# 16_SOLENOID_HB_1.net
KiCad netlist of a schematic drawn in Altium Designer
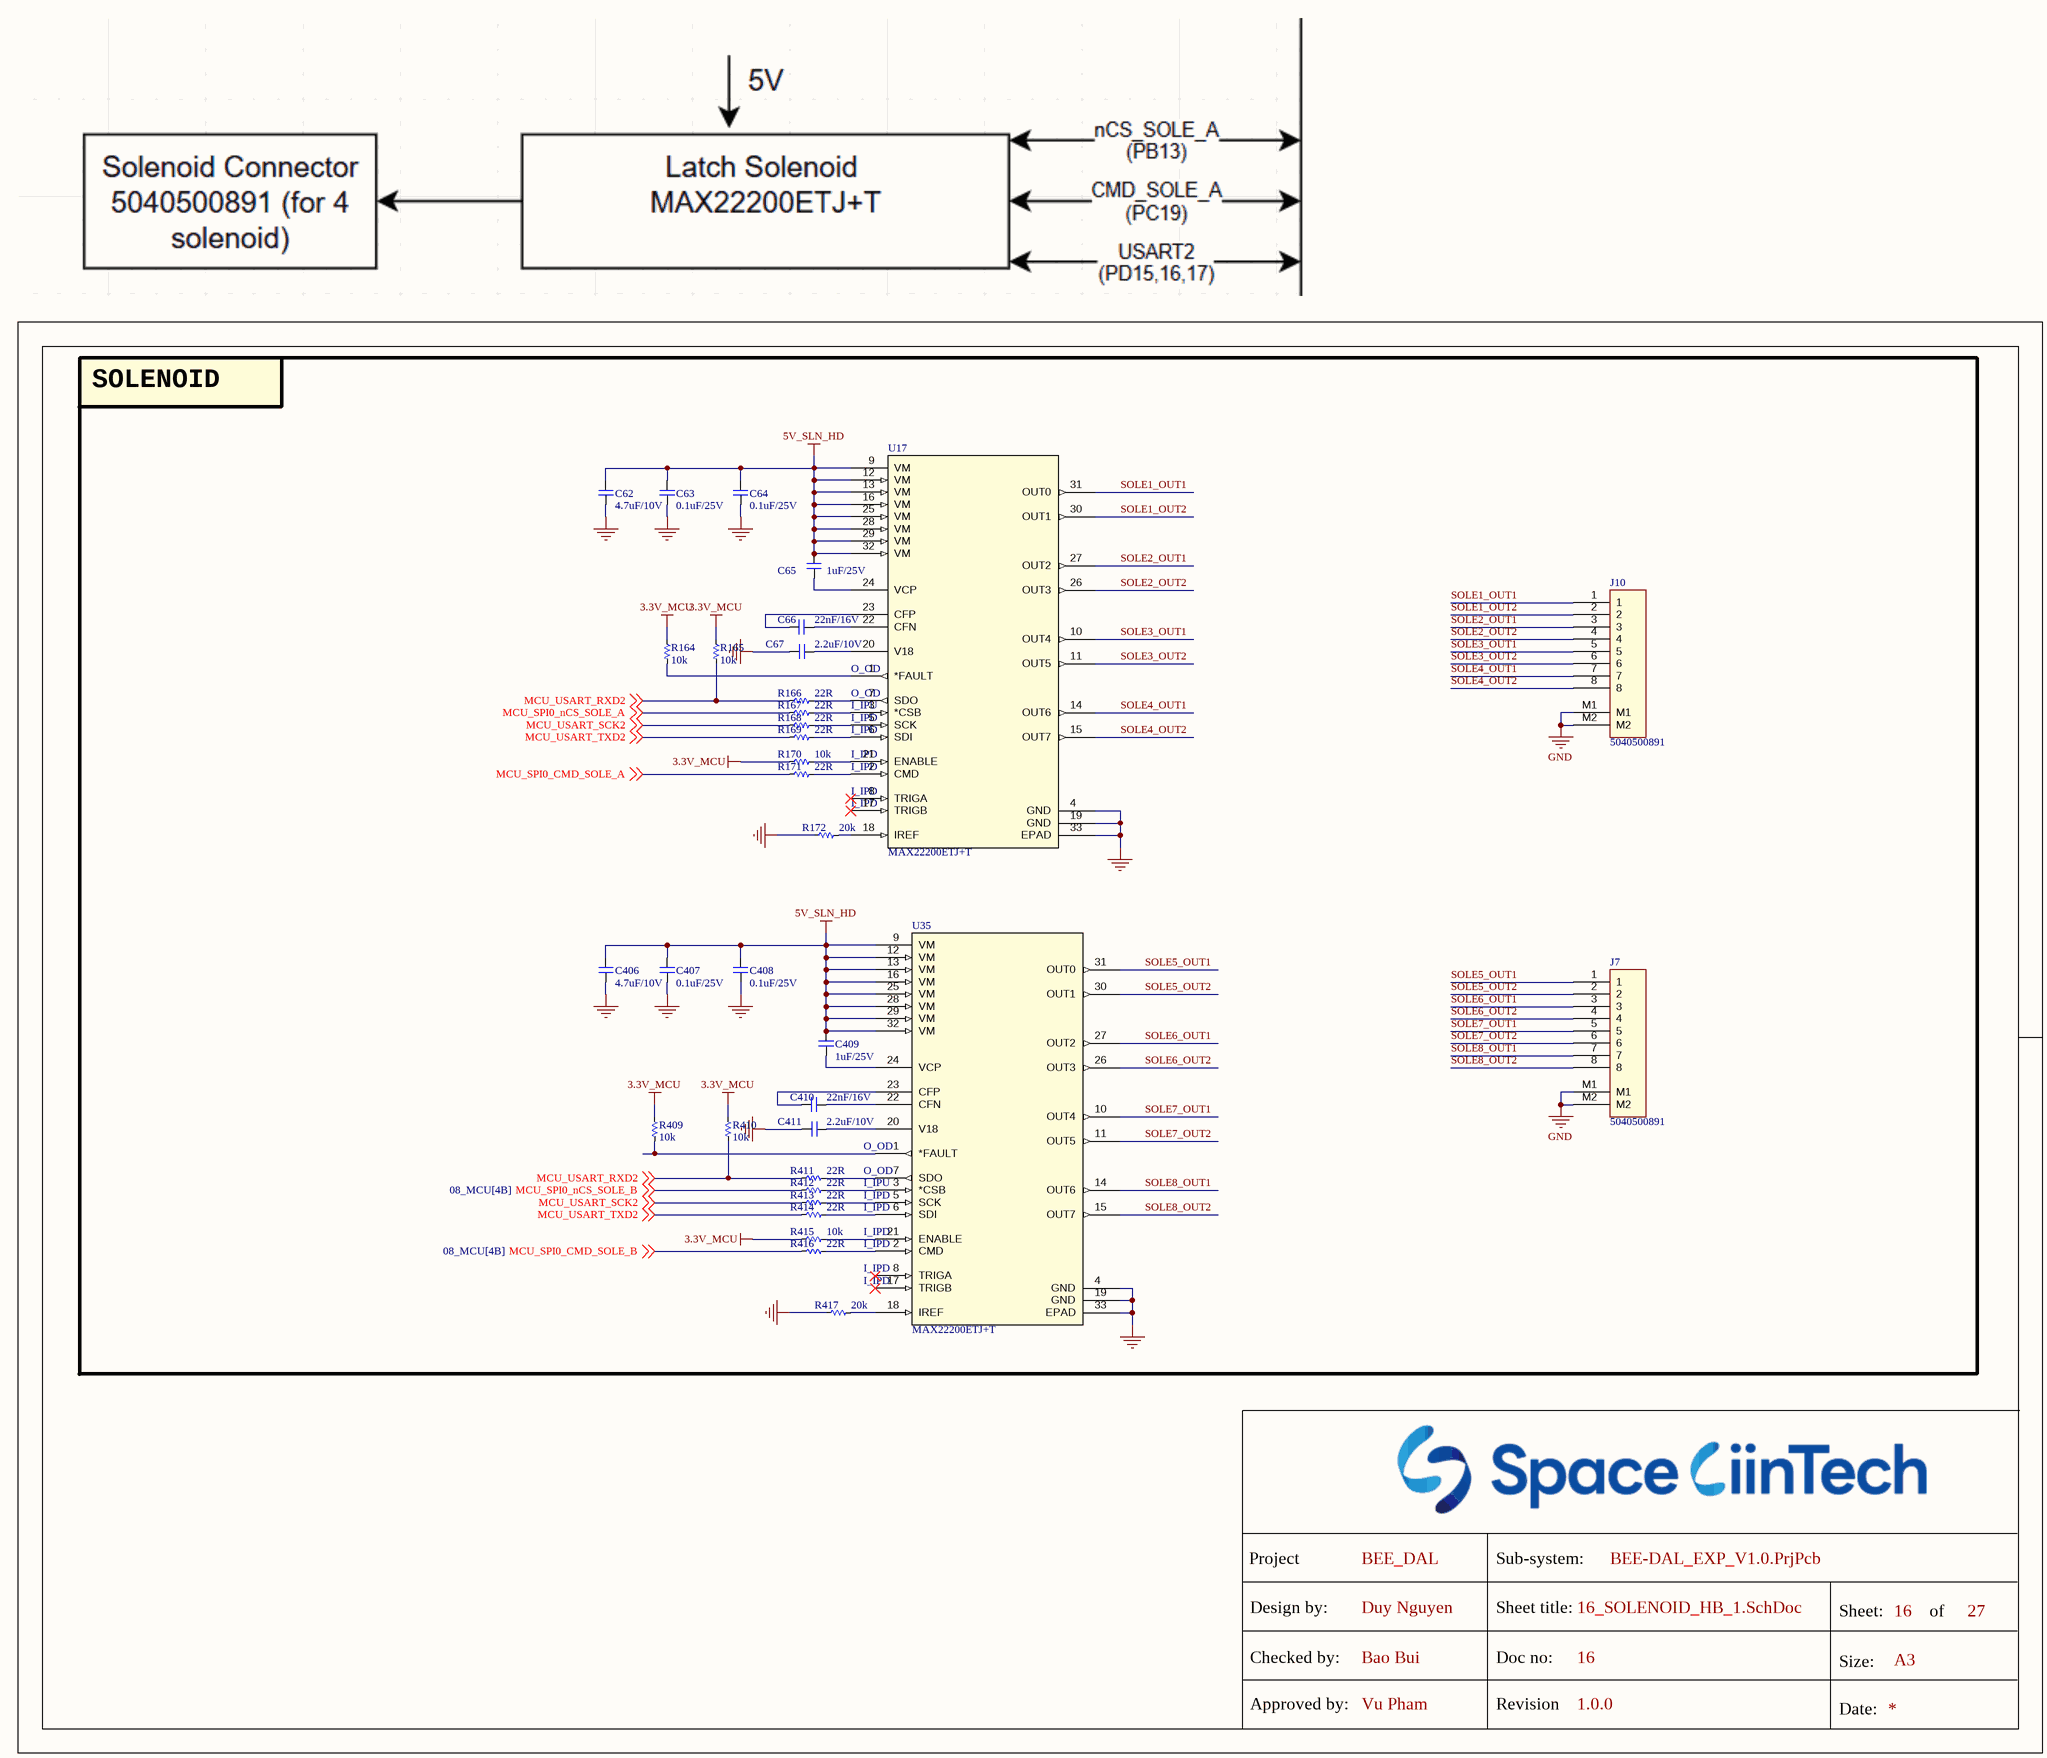
[diagram p0: 16_SOLENOID_HB_1.SchDoc]

(export (version "E")
  (design (tool "Eeschema 10.0.6"))
  (components
    (comp (ref "C62")
      (value "4.7uF/10V")
      (footprint "CAP_C_1005X60")
      (description "CAP")
      (libsource (lib "LABLIB") (part "_CAP_C_2"))
    )
    (comp (ref "C63")
      (value "0.1uF/25V")
      (footprint "CAP_C_1005X60")
      (description "CAP")
      (libsource (lib "LABLIB") (part "_CAP_C_2"))
    )
    (comp (ref "C64")
      (value "0.1uF/25V")
      (footprint "CAP_C_1005X60")
      (description "CAP")
      (libsource (lib "LABLIB") (part "_CAP_C_2"))
    )
    (comp (ref "C65")
      (value "1uF/25V")
      (footprint "CAP_C_1005X60")
      (description "CAP")
      (libsource (lib "LABLIB") (part "_CAP_C_2"))
    )
    (comp (ref "C66")
      (value "22nF/16V")
      (footprint "CAP_C_1005X60")
      (description "CAP CHIP")
      (libsource (lib "LABLIB") (part "_CAP_C_2"))
    )
    (comp (ref "C67")
      (value "2.2uF/10V")
      (footprint "CAP_C_1005X60")
      (description "CAP")
      (libsource (lib "LABLIB") (part "_CAP_C_2"))
    )
    (comp (ref "C406")
      (value "4.7uF/10V")
      (footprint "CAP_C_1005X60")
      (description "CAP")
      (libsource (lib "LABLIB") (part "_CAP_C_2"))
    )
    (comp (ref "C407")
      (value "0.1uF/25V")
      (footprint "CAP_C_1005X60")
      (description "CAP")
      (libsource (lib "LABLIB") (part "_CAP_C_2"))
    )
    (comp (ref "C408")
      (value "0.1uF/25V")
      (footprint "CAP_C_1005X60")
      (description "CAP")
      (libsource (lib "LABLIB") (part "_CAP_C_2"))
    )
    (comp (ref "C409")
      (value "1uF/25V")
      (footprint "CAP_C_1005X60")
      (description "CAP")
      (libsource (lib "LABLIB") (part "_CAP_C_2"))
    )
    (comp (ref "C410")
      (value "22nF/16V")
      (footprint "CAP_C_1005X60")
      (description "CAP CHIP")
      (libsource (lib "LABLIB") (part "_CAP_C_2"))
    )
    (comp (ref "C411")
      (value "2.2uF/10V")
      (footprint "CAP_C_1005X60")
      (description "CAP")
      (libsource (lib "LABLIB") (part "_CAP_C_2"))
    )
    (comp (ref "J7")
      (value "5040500891")
      (footprint "MOLEX_5040500891")
      (libsource (lib "LABLIB") (part "Header 8x1_2M"))
    )
    (comp (ref "J10")
      (value "5040500891")
      (footprint "MOLEX_5040500891")
      (libsource (lib "LABLIB") (part "Header 8x1_2M"))
    )
    (comp (ref "R164")
      (value "10k")
      (footprint "RES_C_1005X40")
      (description "RES")
      (libsource (lib "LABLIB") (part "_RES_B_2"))
    )
    (comp (ref "R165")
      (value "10k")
      (footprint "RES_C_1005X40")
      (description "RES")
      (libsource (lib "LABLIB") (part "_RES_B_2"))
    )
    (comp (ref "R166")
      (value "22R")
      (footprint "RES_C_1005X40")
      (description "RES")
      (libsource (lib "LABLIB") (part "_RES_B_2"))
    )
    (comp (ref "R167")
      (value "22R")
      (footprint "RES_C_1005X40")
      (description "RES")
      (libsource (lib "LABLIB") (part "_RES_B_2"))
    )
    (comp (ref "R168")
      (value "22R")
      (footprint "RES_C_1005X40")
      (description "RES")
      (libsource (lib "LABLIB") (part "_RES_B_2"))
    )
    (comp (ref "R169")
      (value "22R")
      (footprint "RES_C_1005X40")
      (description "RES")
      (libsource (lib "LABLIB") (part "_RES_B_2"))
    )
    (comp (ref "R170")
      (value "10k")
      (footprint "RES_C_1005X40")
      (description "RES")
      (libsource (lib "LABLIB") (part "_RES_B_2"))
    )
    (comp (ref "R171")
      (value "22R")
      (footprint "RES_C_1005X40")
      (description "RES")
      (libsource (lib "LABLIB") (part "_RES_B_2"))
    )
    (comp (ref "R172")
      (value "20k")
      (footprint "RES_C_1005X40")
      (description "RES")
      (libsource (lib "LABLIB") (part "_RES_B_2"))
    )
    (comp (ref "R409")
      (value "10k")
      (footprint "RES_C_1005X40")
      (description "RES")
      (libsource (lib "LABLIB") (part "_RES_B_2"))
    )
    (comp (ref "R410")
      (value "10k")
      (footprint "RES_C_1005X40")
      (description "RES")
      (libsource (lib "LABLIB") (part "_RES_B_2"))
    )
    (comp (ref "R411")
      (value "22R")
      (footprint "RES_C_1005X40")
      (description "RES")
      (libsource (lib "LABLIB") (part "_RES_B_2"))
    )
    (comp (ref "R412")
      (value "22R")
      (footprint "RES_C_1005X40")
      (description "RES")
      (libsource (lib "LABLIB") (part "_RES_B_2"))
    )
    (comp (ref "R413")
      (value "22R")
      (footprint "RES_C_1005X40")
      (description "RES")
      (libsource (lib "LABLIB") (part "_RES_B_2"))
    )
    (comp (ref "R414")
      (value "22R")
      (footprint "RES_C_1005X40")
      (description "RES")
      (libsource (lib "LABLIB") (part "_RES_B_2"))
    )
    (comp (ref "R415")
      (value "10k")
      (footprint "RES_C_1005X40")
      (description "RES")
      (libsource (lib "LABLIB") (part "_RES_B_2"))
    )
    (comp (ref "R416")
      (value "22R")
      (footprint "RES_C_1005X40")
      (description "RES")
      (libsource (lib "LABLIB") (part "_RES_B_2"))
    )
    (comp (ref "R417")
      (value "20k")
      (footprint "RES_C_1005X40")
      (description "RES")
      (libsource (lib "LABLIB") (part "_RES_B_2"))
    )
    (comp (ref "U17")
      (value "MAX22200ETJ+T")
      (footprint "21-0140AK_T3255_8C_MXM")
      (description "36V, 1A Octal Integrated Serial-Controlled Solenoid and Motor Driver")
      (fields (field (name "COPYRIGHT") "Copyright (C) 2026 Ultra Librarian. All rights reserved."))
      (libsource (lib "LABLIB") (part "MAX22200ETJ+T"))
    )
    (comp (ref "U35")
      (value "MAX22200ETJ+T")
      (footprint "21-0140AK_T3255_8C_MXM")
      (description "36V, 1A Octal Integrated Serial-Controlled Solenoid and Motor Driver")
      (fields (field (name "COPYRIGHT") "Copyright (C) 2026 Ultra Librarian. All rights reserved."))
      (libsource (lib "LABLIB") (part "MAX22200ETJ+T"))
    )
  )
  (nets
    (net (code "1") (name "/SOLE1_OUT1") (class "Default")
      (node (ref "J10") (pin "1") (pinfunction "1_1") (pintype "passive"))
      (node (ref "U17") (pin "31") (pinfunction "OUT0_31") (pintype "output"))
    )
    (net (code "2") (name "/SOLE1_OUT2") (class "Default")
      (node (ref "J10") (pin "2") (pinfunction "2_2") (pintype "passive"))
      (node (ref "U17") (pin "30") (pinfunction "OUT1_30") (pintype "output"))
    )
    (net (code "3") (name "/SOLE2_OUT1") (class "Default")
      (node (ref "J10") (pin "3") (pinfunction "3_3") (pintype "passive"))
      (node (ref "U17") (pin "27") (pinfunction "OUT2_27") (pintype "output"))
    )
    (net (code "4") (name "/SOLE2_OUT2") (class "Default")
      (node (ref "J10") (pin "4") (pinfunction "4_4") (pintype "passive"))
      (node (ref "U17") (pin "26") (pinfunction "OUT3_26") (pintype "output"))
    )
    (net (code "5") (name "/SOLE3_OUT1") (class "Default")
      (node (ref "J10") (pin "5") (pinfunction "5_5") (pintype "passive"))
      (node (ref "U17") (pin "10") (pinfunction "OUT4_10") (pintype "output"))
    )
    (net (code "6") (name "/SOLE3_OUT2") (class "Default")
      (node (ref "J10") (pin "6") (pinfunction "6_6") (pintype "passive"))
      (node (ref "U17") (pin "11") (pinfunction "OUT5_11") (pintype "output"))
    )
    (net (code "7") (name "/SOLE4_OUT1") (class "Default")
      (node (ref "J10") (pin "7") (pinfunction "7_7") (pintype "passive"))
      (node (ref "U17") (pin "14") (pinfunction "OUT6_14") (pintype "output"))
    )
    (net (code "8") (name "/SOLE4_OUT2") (class "Default")
      (node (ref "J10") (pin "8") (pinfunction "8_8") (pintype "passive"))
      (node (ref "U17") (pin "15") (pinfunction "OUT7_15") (pintype "output"))
    )
    (net (code "9") (name "/SOLE5_OUT1") (class "Default")
      (node (ref "J7") (pin "1") (pinfunction "1_1") (pintype "passive"))
      (node (ref "U35") (pin "31") (pinfunction "OUT0_31") (pintype "output"))
    )
    (net (code "10") (name "/SOLE5_OUT2") (class "Default")
      (node (ref "J7") (pin "2") (pinfunction "2_2") (pintype "passive"))
      (node (ref "U35") (pin "30") (pinfunction "OUT1_30") (pintype "output"))
    )
    (net (code "11") (name "/SOLE6_OUT1") (class "Default")
      (node (ref "J7") (pin "3") (pinfunction "3_3") (pintype "passive"))
      (node (ref "U35") (pin "27") (pinfunction "OUT2_27") (pintype "output"))
    )
    (net (code "12") (name "/SOLE6_OUT2") (class "Default")
      (node (ref "J7") (pin "4") (pinfunction "4_4") (pintype "passive"))
      (node (ref "U35") (pin "26") (pinfunction "OUT3_26") (pintype "output"))
    )
    (net (code "13") (name "/SOLE7_OUT1") (class "Default")
      (node (ref "J7") (pin "5") (pinfunction "5_5") (pintype "passive"))
      (node (ref "U35") (pin "10") (pinfunction "OUT4_10") (pintype "output"))
    )
    (net (code "14") (name "/SOLE7_OUT2") (class "Default")
      (node (ref "J7") (pin "6") (pinfunction "6_6") (pintype "passive"))
      (node (ref "U35") (pin "11") (pinfunction "OUT5_11") (pintype "output"))
    )
    (net (code "15") (name "/SOLE8_OUT1") (class "Default")
      (node (ref "J7") (pin "7") (pinfunction "7_7") (pintype "passive"))
      (node (ref "U35") (pin "14") (pinfunction "OUT6_14") (pintype "output"))
    )
    (net (code "16") (name "/SOLE8_OUT2") (class "Default")
      (node (ref "J7") (pin "8") (pinfunction "8_8") (pintype "passive"))
      (node (ref "U35") (pin "15") (pinfunction "OUT7_15") (pintype "output"))
    )
    (net (code "17") (name "3.3V_MCU") (class "Default")
      (node (ref "R164") (pin "1") (pinfunction "1_1") (pintype "passive"))
      (node (ref "R165") (pin "1") (pinfunction "1_1") (pintype "passive"))
      (node (ref "R170") (pin "1") (pinfunction "1_1") (pintype "passive"))
      (node (ref "R409") (pin "1") (pinfunction "1_1") (pintype "passive"))
      (node (ref "R410") (pin "1") (pinfunction "1_1") (pintype "passive"))
      (node (ref "R415") (pin "1") (pinfunction "1_1") (pintype "passive"))
    )
    (net (code "18") (name "5V_SLN_HD") (class "Default")
      (node (ref "C406") (pin "2") (pinfunction "2_2") (pintype "passive"))
      (node (ref "C407") (pin "2") (pinfunction "2_2") (pintype "passive"))
      (node (ref "C408") (pin "2") (pinfunction "2_2") (pintype "passive"))
      (node (ref "C409") (pin "2") (pinfunction "2_2") (pintype "passive"))
      (node (ref "C62") (pin "2") (pinfunction "2_2") (pintype "passive"))
      (node (ref "C63") (pin "2") (pinfunction "2_2") (pintype "passive"))
      (node (ref "C64") (pin "2") (pinfunction "2_2") (pintype "passive"))
      (node (ref "C65") (pin "2") (pinfunction "2_2") (pintype "passive"))
      (node (ref "U17") (pin "12") (pinfunction "VM_12") (pintype "input"))
      (node (ref "U17") (pin "13") (pinfunction "VM_13") (pintype "input"))
      (node (ref "U17") (pin "16") (pinfunction "VM_16") (pintype "input"))
      (node (ref "U17") (pin "25") (pinfunction "VM_25") (pintype "input"))
      (node (ref "U17") (pin "28") (pinfunction "VM_28") (pintype "input"))
      (node (ref "U17") (pin "29") (pinfunction "VM_29") (pintype "input"))
      (node (ref "U17") (pin "32") (pinfunction "VM_32") (pintype "input"))
      (node (ref "U17") (pin "9") (pinfunction "VM_9") (pintype "power_in"))
      (node (ref "U35") (pin "12") (pinfunction "VM_12") (pintype "input"))
      (node (ref "U35") (pin "13") (pinfunction "VM_13") (pintype "input"))
      (node (ref "U35") (pin "16") (pinfunction "VM_16") (pintype "input"))
      (node (ref "U35") (pin "25") (pinfunction "VM_25") (pintype "input"))
      (node (ref "U35") (pin "28") (pinfunction "VM_28") (pintype "input"))
      (node (ref "U35") (pin "29") (pinfunction "VM_29") (pintype "input"))
      (node (ref "U35") (pin "32") (pinfunction "VM_32") (pintype "input"))
      (node (ref "U35") (pin "9") (pinfunction "VM_9") (pintype "power_in"))
    )
    (net (code "19") (name "GND") (class "Default")
      (node (ref "C406") (pin "1") (pinfunction "1_1") (pintype "passive"))
      (node (ref "C407") (pin "1") (pinfunction "1_1") (pintype "passive"))
      (node (ref "C408") (pin "1") (pinfunction "1_1") (pintype "passive"))
      (node (ref "C411") (pin "1") (pinfunction "1_1") (pintype "passive"))
      (node (ref "C62") (pin "1") (pinfunction "1_1") (pintype "passive"))
      (node (ref "C63") (pin "1") (pinfunction "1_1") (pintype "passive"))
      (node (ref "C64") (pin "1") (pinfunction "1_1") (pintype "passive"))
      (node (ref "C67") (pin "1") (pinfunction "1_1") (pintype "passive"))
      (node (ref "J10") (pin "M1") (pinfunction "M1_M1") (pintype "passive"))
      (node (ref "J10") (pin "M2") (pinfunction "M2_M2") (pintype "passive"))
      (node (ref "J7") (pin "M1") (pinfunction "M1_M1") (pintype "passive"))
      (node (ref "J7") (pin "M2") (pinfunction "M2_M2") (pintype "passive"))
      (node (ref "R172") (pin "1") (pinfunction "1_1") (pintype "passive"))
      (node (ref "R417") (pin "1") (pinfunction "1_1") (pintype "passive"))
      (node (ref "U17") (pin "19") (pinfunction "GND_19") (pintype "power_in"))
      (node (ref "U17") (pin "33") (pinfunction "EPAD_33") (pintype "power_in"))
      (node (ref "U17") (pin "4") (pinfunction "GND_4") (pintype "power_in"))
      (node (ref "U35") (pin "19") (pinfunction "GND_19") (pintype "power_in"))
      (node (ref "U35") (pin "33") (pinfunction "EPAD_33") (pintype "power_in"))
      (node (ref "U35") (pin "4") (pinfunction "GND_4") (pintype "power_in"))
    )
    (net (code "20") (name "MCU_SPI0_CMD_SOLE_A") (class "Default")
      (node (ref "R171") (pin "1") (pinfunction "1_1") (pintype "passive"))
    )
    (net (code "21") (name "MCU_SPI0_CMD_SOLE_B") (class "Default")
      (node (ref "R416") (pin "1") (pinfunction "1_1") (pintype "passive"))
    )
    (net (code "22") (name "MCU_SPI0_nCS_SOLE_A") (class "Default")
      (node (ref "R167") (pin "1") (pinfunction "1_1") (pintype "passive"))
    )
    (net (code "23") (name "MCU_SPI0_nCS_SOLE_B") (class "Default")
      (node (ref "R412") (pin "1") (pinfunction "1_1") (pintype "passive"))
    )
    (net (code "24") (name "MCU_USART_RXD2") (class "Default")
      (node (ref "R165") (pin "2") (pinfunction "2_2") (pintype "passive"))
      (node (ref "R166") (pin "1") (pinfunction "1_1") (pintype "passive"))
      (node (ref "R410") (pin "2") (pinfunction "2_2") (pintype "passive"))
      (node (ref "R411") (pin "1") (pinfunction "1_1") (pintype "passive"))
    )
    (net (code "25") (name "MCU_USART_SCK2") (class "Default")
      (node (ref "R168") (pin "1") (pinfunction "1_1") (pintype "passive"))
      (node (ref "R413") (pin "1") (pinfunction "1_1") (pintype "passive"))
    )
    (net (code "26") (name "MCU_USART_TXD2") (class "Default")
      (node (ref "R169") (pin "1") (pinfunction "1_1") (pintype "passive"))
      (node (ref "R414") (pin "1") (pinfunction "1_1") (pintype "passive"))
    )
    (net (code "27") (name "Net-(U17-*CSB)") (class "Default")
      (node (ref "R167") (pin "2") (pinfunction "2_2") (pintype "passive"))
      (node (ref "U17") (pin "3") (pinfunction "*CSB_3") (pintype "input"))
    )
    (net (code "28") (name "Net-(U17-*FAULT)") (class "Default")
      (node (ref "R164") (pin "2") (pinfunction "2_2") (pintype "passive"))
      (node (ref "U17") (pin "1") (pinfunction "*FAULT_1") (pintype "output"))
    )
    (net (code "29") (name "Net-(U17-CFN)") (class "Default")
      (node (ref "C66") (pin "1") (pinfunction "1_1") (pintype "passive"))
      (node (ref "U17") (pin "22") (pinfunction "CFN_22") (pintype "power_in"))
    )
    (net (code "30") (name "Net-(U17-CFP)") (class "Default")
      (node (ref "C66") (pin "2") (pinfunction "2_2") (pintype "passive"))
      (node (ref "U17") (pin "23") (pinfunction "CFP_23") (pintype "power_in"))
    )
    (net (code "31") (name "Net-(U17-CMD)") (class "Default")
      (node (ref "R171") (pin "2") (pinfunction "2_2") (pintype "passive"))
      (node (ref "U17") (pin "2") (pinfunction "CMD_2") (pintype "input"))
    )
    (net (code "32") (name "Net-(U17-ENABLE)") (class "Default")
      (node (ref "R170") (pin "2") (pinfunction "2_2") (pintype "passive"))
      (node (ref "U17") (pin "21") (pinfunction "ENABLE_21") (pintype "input"))
    )
    (net (code "33") (name "Net-(U17-IREF)") (class "Default")
      (node (ref "R172") (pin "2") (pinfunction "2_2") (pintype "passive"))
      (node (ref "U17") (pin "18") (pinfunction "IREF_18") (pintype "input"))
    )
    (net (code "34") (name "Net-(U17-SCK)") (class "Default")
      (node (ref "R168") (pin "2") (pinfunction "2_2") (pintype "passive"))
      (node (ref "U17") (pin "5") (pinfunction "SCK_5") (pintype "input"))
    )
    (net (code "35") (name "Net-(U17-SDI)") (class "Default")
      (node (ref "R169") (pin "2") (pinfunction "2_2") (pintype "passive"))
      (node (ref "U17") (pin "6") (pinfunction "SDI_6") (pintype "input"))
    )
    (net (code "36") (name "Net-(U17-SDO)") (class "Default")
      (node (ref "R166") (pin "2") (pinfunction "2_2") (pintype "passive"))
      (node (ref "U17") (pin "7") (pinfunction "SDO_7") (pintype "output"))
    )
    (net (code "37") (name "Net-(U17-V18)") (class "Default")
      (node (ref "C67") (pin "2") (pinfunction "2_2") (pintype "passive"))
      (node (ref "U17") (pin "20") (pinfunction "V18_20") (pintype "power_in"))
    )
    (net (code "38") (name "Net-(U17-VCP)") (class "Default")
      (node (ref "C65") (pin "1") (pinfunction "1_1") (pintype "passive"))
      (node (ref "U17") (pin "24") (pinfunction "VCP_24") (pintype "power_in"))
    )
    (net (code "39") (name "Net-(U35-*CSB)") (class "Default")
      (node (ref "R412") (pin "2") (pinfunction "2_2") (pintype "passive"))
      (node (ref "U35") (pin "3") (pinfunction "*CSB_3") (pintype "input"))
    )
    (net (code "40") (name "Net-(U35-*FAULT)") (class "Default")
      (node (ref "R409") (pin "2") (pinfunction "2_2") (pintype "passive"))
      (node (ref "U35") (pin "1") (pinfunction "*FAULT_1") (pintype "output"))
    )
    (net (code "41") (name "Net-(U35-CFN)") (class "Default")
      (node (ref "C410") (pin "1") (pinfunction "1_1") (pintype "passive"))
      (node (ref "U35") (pin "22") (pinfunction "CFN_22") (pintype "power_in"))
    )
    (net (code "42") (name "Net-(U35-CFP)") (class "Default")
      (node (ref "C410") (pin "2") (pinfunction "2_2") (pintype "passive"))
      (node (ref "U35") (pin "23") (pinfunction "CFP_23") (pintype "power_in"))
    )
    (net (code "43") (name "Net-(U35-CMD)") (class "Default")
      (node (ref "R416") (pin "2") (pinfunction "2_2") (pintype "passive"))
      (node (ref "U35") (pin "2") (pinfunction "CMD_2") (pintype "input"))
    )
    (net (code "44") (name "Net-(U35-ENABLE)") (class "Default")
      (node (ref "R415") (pin "2") (pinfunction "2_2") (pintype "passive"))
      (node (ref "U35") (pin "21") (pinfunction "ENABLE_21") (pintype "input"))
    )
    (net (code "45") (name "Net-(U35-IREF)") (class "Default")
      (node (ref "R417") (pin "2") (pinfunction "2_2") (pintype "passive"))
      (node (ref "U35") (pin "18") (pinfunction "IREF_18") (pintype "input"))
    )
    (net (code "46") (name "Net-(U35-SCK)") (class "Default")
      (node (ref "R413") (pin "2") (pinfunction "2_2") (pintype "passive"))
      (node (ref "U35") (pin "5") (pinfunction "SCK_5") (pintype "input"))
    )
    (net (code "47") (name "Net-(U35-SDI)") (class "Default")
      (node (ref "R414") (pin "2") (pinfunction "2_2") (pintype "passive"))
      (node (ref "U35") (pin "6") (pinfunction "SDI_6") (pintype "input"))
    )
    (net (code "48") (name "Net-(U35-SDO)") (class "Default")
      (node (ref "R411") (pin "2") (pinfunction "2_2") (pintype "passive"))
      (node (ref "U35") (pin "7") (pinfunction "SDO_7") (pintype "output"))
    )
    (net (code "49") (name "Net-(U35-V18)") (class "Default")
      (node (ref "C411") (pin "2") (pinfunction "2_2") (pintype "passive"))
      (node (ref "U35") (pin "20") (pinfunction "V18_20") (pintype "power_in"))
    )
    (net (code "50") (name "Net-(U35-VCP)") (class "Default")
      (node (ref "C409") (pin "1") (pinfunction "1_1") (pintype "passive"))
      (node (ref "U35") (pin "24") (pinfunction "VCP_24") (pintype "power_in"))
    )
    (net (code "51") (name "unconnected-(U17-TRIGA-Pad8)") (class "Default")
      (node (ref "U17") (pin "8") (pinfunction "TRIGA_8") (pintype "input+no_connect"))
    )
    (net (code "52") (name "unconnected-(U17-TRIGB-Pad17)") (class "Default")
      (node (ref "U17") (pin "17") (pinfunction "TRIGB_17") (pintype "input+no_connect"))
    )
    (net (code "53") (name "unconnected-(U35-TRIGA-Pad8)") (class "Default")
      (node (ref "U35") (pin "8") (pinfunction "TRIGA_8") (pintype "input+no_connect"))
    )
    (net (code "54") (name "unconnected-(U35-TRIGB-Pad17)") (class "Default")
      (node (ref "U35") (pin "17") (pinfunction "TRIGB_17") (pintype "input+no_connect"))
    )
  )
)
